# Tapuino_1_2_con_botones.net
KiCad netlist of a schematic drawn in EAGLE
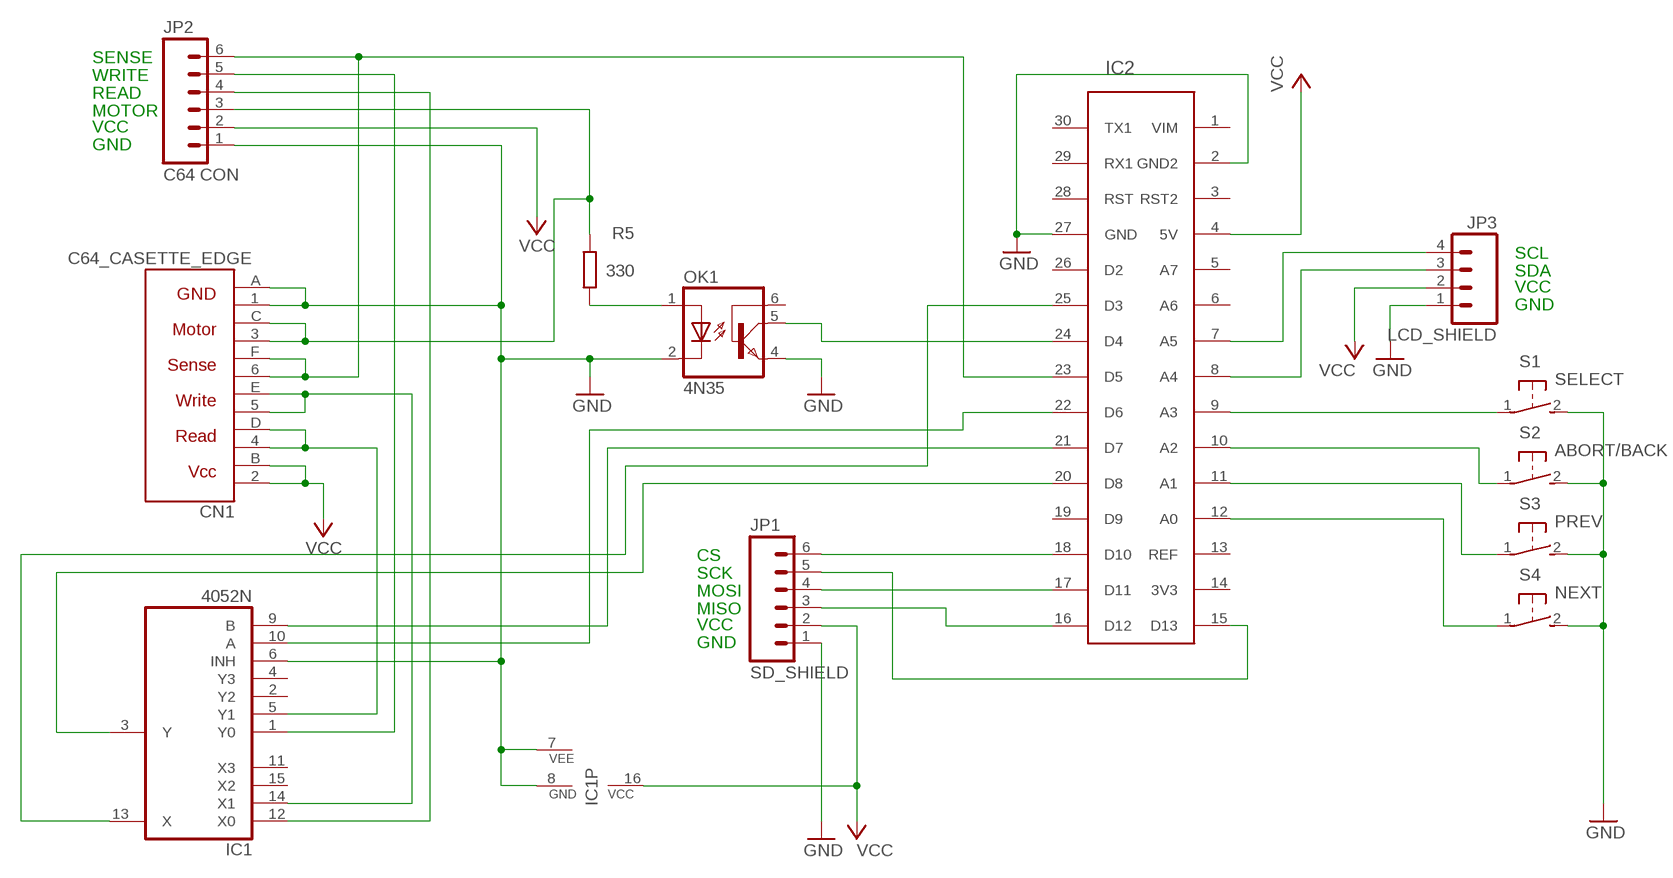
[diagram p0: schematic, sheet 1]

(export (version "E")
  (design (tool "Eeschema 10.0.6"))
  (components
    (comp (ref "CN1")
      (value "C64_CASETTE_EDGE")
      (footprint "eagle-import:C64_CASSETTE")
      (libsource (lib "eagle-import") (part "C64_CASETTE_EDGE"))
    )
    (comp (ref "IC1")
      (value "4052N")
      (footprint "eagle-import:DIL16")
      (libsource (lib "eagle-import") (part "4052N"))
    )
    (comp (ref "IC2")
      (value "ARDUINO_NANO_V3")
      (footprint "eagle-import:NANO_V3")
      (libsource (lib "eagle-import") (part "ARDUINO_NANO_V3"))
    )
    (comp (ref "JP1")
      (value "SD_SHIELD")
      (footprint "eagle-import:1X06_LOCK_LONGPADS")
      (libsource (lib "eagle-import") (part "M06LOCK_LONGPADS"))
    )
    (comp (ref "JP2")
      (value "C64 CON")
      (footprint "eagle-import:1X06_LOCK_LONGPADS")
      (libsource (lib "eagle-import") (part "M06LOCK_LONGPADS"))
    )
    (comp (ref "JP3")
      (value "LCD_SHIELD")
      (footprint "eagle-import:1X04_LOCK_LONGPADS")
      (libsource (lib "eagle-import") (part "M04LOCK_LONGPADS"))
    )
    (comp (ref "OK1")
      (value "4N35")
      (footprint "eagle-import:DIL06")
      (fields (field (name "MF") "FAIRCHILD SEMICONDUCTOR"))
      (libsource (lib "eagle-import") (part "4N35"))
    )
    (comp (ref "R5")
      (value "330")
      (footprint "eagle-import:0207_10")
      (libsource (lib "eagle-import") (part "R-EU_0207/10"))
    )
    (comp (ref "S1")
      (value "SELECT")
      (footprint "eagle-import:B3F-31XX")
      (fields (field (name "MPN") "B3F-3100"))
      (libsource (lib "eagle-import") (part "31-XX"))
    )
    (comp (ref "S2")
      (value "ABORT/BACK")
      (footprint "eagle-import:B3F-31XX")
      (fields (field (name "MPN") "B3F-3100"))
      (libsource (lib "eagle-import") (part "31-XX"))
    )
    (comp (ref "S3")
      (value "PREV")
      (footprint "eagle-import:B3F-31XX")
      (fields (field (name "MPN") "B3F-3100"))
      (libsource (lib "eagle-import") (part "31-XX"))
    )
    (comp (ref "S4")
      (value "NEXT")
      (footprint "eagle-import:B3F-31XX")
      (fields (field (name "MPN") "B3F-3100"))
      (libsource (lib "eagle-import") (part "31-XX"))
    )
  )
  (nets
    (net (code "1") (name "GND") (class "Default")
      (node (ref "CN1") (pin "1") (pinfunction "GND1_1") (pintype "power_in"))
      (node (ref "CN1") (pin "A") (pinfunction "GND2_A") (pintype "power_in"))
      (node (ref "IC1") (pin "6") (pinfunction "INH_6") (pintype "input"))
      (node (ref "IC1") (pin "7") (pinfunction "VEE_7") (pintype "power_in"))
      (node (ref "IC1") (pin "8") (pinfunction "GND_8") (pintype "power_in"))
      (node (ref "IC2") (pin "2") (pinfunction "GND2_2") (pintype "bidirectional"))
      (node (ref "IC2") (pin "27") (pinfunction "GND_27") (pintype "bidirectional"))
      (node (ref "JP1") (pin "1") (pinfunction "1_1") (pintype "passive"))
      (node (ref "JP2") (pin "1") (pinfunction "1_1") (pintype "passive"))
      (node (ref "JP3") (pin "1") (pinfunction "1_1") (pintype "passive"))
      (node (ref "OK1") (pin "2") (pinfunction "C_2") (pintype "passive"))
      (node (ref "OK1") (pin "4") (pinfunction "EMI_4") (pintype "passive"))
      (node (ref "S1") (pin "2") (pinfunction "S_2") (pintype "passive"))
      (node (ref "S2") (pin "2") (pinfunction "S_2") (pintype "passive"))
      (node (ref "S3") (pin "2") (pinfunction "S_2") (pintype "passive"))
      (node (ref "S4") (pin "2") (pinfunction "S_2") (pintype "passive"))
    )
    (net (code "2") (name "Net-(CN1-MOTOR1)") (class "Default")
      (node (ref "CN1") (pin "3") (pinfunction "MOTOR1_3") (pintype "output"))
      (node (ref "CN1") (pin "C") (pinfunction "MOTOR2_C") (pintype "output"))
      (node (ref "JP2") (pin "3") (pinfunction "3_3") (pintype "passive"))
      (node (ref "R5") (pin "2") (pinfunction "2_2") (pintype "passive"))
    )
    (net (code "3") (name "Net-(CN1-READ1)") (class "Default")
      (node (ref "CN1") (pin "4") (pinfunction "READ1_4") (pintype "output"))
      (node (ref "CN1") (pin "D") (pinfunction "READ2_D") (pintype "output"))
      (node (ref "IC1") (pin "5") (pinfunction "Y1_5") (pintype "bidirectional"))
    )
    (net (code "4") (name "Net-(CN1-SENSE1)") (class "Default")
      (node (ref "CN1") (pin "6") (pinfunction "SENSE1_6") (pintype "input"))
      (node (ref "CN1") (pin "F") (pinfunction "SENSE2_F") (pintype "input"))
      (node (ref "IC2") (pin "23") (pinfunction "D5_23") (pintype "bidirectional"))
      (node (ref "JP2") (pin "6") (pinfunction "6_6") (pintype "passive"))
    )
    (net (code "5") (name "Net-(CN1-WRITE1)") (class "Default")
      (node (ref "CN1") (pin "5") (pinfunction "WRITE1_5") (pintype "input"))
      (node (ref "CN1") (pin "E") (pinfunction "WRITE2_E") (pintype "input"))
      (node (ref "IC1") (pin "14") (pinfunction "X1_14") (pintype "bidirectional"))
    )
    (net (code "6") (name "Net-(IC1A-A)") (class "Default")
      (node (ref "IC1") (pin "10") (pinfunction "A_10") (pintype "input"))
      (node (ref "IC2") (pin "22") (pinfunction "D6_22") (pintype "bidirectional"))
    )
    (net (code "7") (name "Net-(IC1A-B)") (class "Default")
      (node (ref "IC1") (pin "9") (pinfunction "B_9") (pintype "input"))
      (node (ref "IC2") (pin "21") (pinfunction "D7_21") (pintype "bidirectional"))
    )
    (net (code "8") (name "Net-(IC1A-X)") (class "Default")
      (node (ref "IC1") (pin "13") (pinfunction "X_13") (pintype "bidirectional"))
      (node (ref "IC2") (pin "25") (pinfunction "D3_25") (pintype "bidirectional"))
    )
    (net (code "9") (name "Net-(IC1A-X0)") (class "Default")
      (node (ref "IC1") (pin "12") (pinfunction "X0_12") (pintype "bidirectional"))
      (node (ref "JP2") (pin "4") (pinfunction "4_4") (pintype "passive"))
    )
    (net (code "10") (name "Net-(IC1A-Y)") (class "Default")
      (node (ref "IC1") (pin "3") (pinfunction "Y_3") (pintype "bidirectional"))
      (node (ref "IC2") (pin "20") (pinfunction "D8_20") (pintype "bidirectional"))
    )
    (net (code "11") (name "Net-(IC1A-Y0)") (class "Default")
      (node (ref "IC1") (pin "1") (pinfunction "Y0_1") (pintype "bidirectional"))
      (node (ref "JP2") (pin "5") (pinfunction "5_5") (pintype "passive"))
    )
    (net (code "12") (name "Net-(IC2-A0)") (class "Default")
      (node (ref "IC2") (pin "12") (pinfunction "A0_12") (pintype "bidirectional"))
      (node (ref "S4") (pin "1") (pinfunction "P_1") (pintype "passive"))
    )
    (net (code "13") (name "Net-(IC2-A1)") (class "Default")
      (node (ref "IC2") (pin "11") (pinfunction "A1_11") (pintype "bidirectional"))
      (node (ref "S3") (pin "1") (pinfunction "P_1") (pintype "passive"))
    )
    (net (code "14") (name "Net-(IC2-A2)") (class "Default")
      (node (ref "IC2") (pin "10") (pinfunction "A2_10") (pintype "bidirectional"))
      (node (ref "S2") (pin "1") (pinfunction "P_1") (pintype "passive"))
    )
    (net (code "15") (name "Net-(IC2-A3)") (class "Default")
      (node (ref "IC2") (pin "9") (pinfunction "A3_9") (pintype "bidirectional"))
      (node (ref "S1") (pin "1") (pinfunction "P_1") (pintype "passive"))
    )
    (net (code "16") (name "Net-(IC2-A4)") (class "Default")
      (node (ref "IC2") (pin "8") (pinfunction "A4_8") (pintype "bidirectional"))
      (node (ref "JP3") (pin "3") (pinfunction "3_3") (pintype "passive"))
    )
    (net (code "17") (name "Net-(IC2-A5)") (class "Default")
      (node (ref "IC2") (pin "7") (pinfunction "A5_7") (pintype "bidirectional"))
      (node (ref "JP3") (pin "4") (pinfunction "4_4") (pintype "passive"))
    )
    (net (code "18") (name "Net-(IC2-D4)") (class "Default")
      (node (ref "IC2") (pin "24") (pinfunction "D4_24") (pintype "bidirectional"))
      (node (ref "OK1") (pin "5") (pinfunction "COL_5") (pintype "passive"))
    )
    (net (code "19") (name "Net-(IC2-D10)") (class "Default")
      (node (ref "IC2") (pin "18") (pinfunction "D10_18") (pintype "bidirectional"))
      (node (ref "JP1") (pin "6") (pinfunction "6_6") (pintype "passive"))
    )
    (net (code "20") (name "Net-(IC2-D11)") (class "Default")
      (node (ref "IC2") (pin "17") (pinfunction "D11_17") (pintype "bidirectional"))
      (node (ref "JP1") (pin "4") (pinfunction "4_4") (pintype "passive"))
    )
    (net (code "21") (name "Net-(IC2-D12)") (class "Default")
      (node (ref "IC2") (pin "16") (pinfunction "D12_16") (pintype "bidirectional"))
      (node (ref "JP1") (pin "3") (pinfunction "3_3") (pintype "passive"))
    )
    (net (code "22") (name "Net-(IC2-D13)") (class "Default")
      (node (ref "IC2") (pin "15") (pinfunction "D13_15") (pintype "bidirectional"))
      (node (ref "JP1") (pin "5") (pinfunction "5_5") (pintype "passive"))
    )
    (net (code "23") (name "Net-(OK1-A)") (class "Default")
      (node (ref "OK1") (pin "1") (pinfunction "A_1") (pintype "passive"))
      (node (ref "R5") (pin "1") (pinfunction "1_1") (pintype "passive"))
    )
    (net (code "24") (name "VCC") (class "Default")
      (node (ref "CN1") (pin "2") (pinfunction "VCC1_2") (pintype "power_in"))
      (node (ref "CN1") (pin "B") (pinfunction "VCC2_B") (pintype "power_in"))
      (node (ref "IC1") (pin "16") (pinfunction "VCC_16") (pintype "power_in"))
      (node (ref "IC2") (pin "4") (pinfunction "5V_4") (pintype "bidirectional"))
      (node (ref "JP1") (pin "2") (pinfunction "2_2") (pintype "passive"))
      (node (ref "JP2") (pin "2") (pinfunction "2_2") (pintype "passive"))
      (node (ref "JP3") (pin "2") (pinfunction "2_2") (pintype "passive"))
    )
    (net (code "25") (name "unconnected-(IC1A-X2-Pad15)") (class "Default")
      (node (ref "IC1") (pin "15") (pinfunction "X2_15") (pintype "bidirectional"))
    )
    (net (code "26") (name "unconnected-(IC1A-X3-Pad11)") (class "Default")
      (node (ref "IC1") (pin "11") (pinfunction "X3_11") (pintype "bidirectional"))
    )
    (net (code "27") (name "unconnected-(IC1A-Y2-Pad2)") (class "Default")
      (node (ref "IC1") (pin "2") (pinfunction "Y2_2") (pintype "bidirectional"))
    )
    (net (code "28") (name "unconnected-(IC1A-Y3-Pad4)") (class "Default")
      (node (ref "IC1") (pin "4") (pinfunction "Y3_4") (pintype "bidirectional"))
    )
    (net (code "29") (name "unconnected-(IC2-3V3-Pad14)") (class "Default")
      (node (ref "IC2") (pin "14") (pinfunction "3V3_14") (pintype "bidirectional"))
    )
    (net (code "30") (name "unconnected-(IC2-A6-Pad6)") (class "Default")
      (node (ref "IC2") (pin "6") (pinfunction "A6_6") (pintype "bidirectional"))
    )
    (net (code "31") (name "unconnected-(IC2-A7-Pad5)") (class "Default")
      (node (ref "IC2") (pin "5") (pinfunction "A7_5") (pintype "bidirectional"))
    )
    (net (code "32") (name "unconnected-(IC2-D2-Pad26)") (class "Default")
      (node (ref "IC2") (pin "26") (pinfunction "D2_26") (pintype "bidirectional"))
    )
    (net (code "33") (name "unconnected-(IC2-D9-Pad19)") (class "Default")
      (node (ref "IC2") (pin "19") (pinfunction "D9_19") (pintype "bidirectional"))
    )
    (net (code "34") (name "unconnected-(IC2-REF-Pad13)") (class "Default")
      (node (ref "IC2") (pin "13") (pinfunction "REF_13") (pintype "bidirectional"))
    )
    (net (code "35") (name "unconnected-(IC2-RST-Pad28)") (class "Default")
      (node (ref "IC2") (pin "28") (pinfunction "RST_28") (pintype "bidirectional"))
    )
    (net (code "36") (name "unconnected-(IC2-RST2-Pad3)") (class "Default")
      (node (ref "IC2") (pin "3") (pinfunction "RST2_3") (pintype "bidirectional"))
    )
    (net (code "37") (name "unconnected-(IC2-RX1-Pad29)") (class "Default")
      (node (ref "IC2") (pin "29") (pinfunction "RX1_29") (pintype "bidirectional"))
    )
    (net (code "38") (name "unconnected-(IC2-TX1-Pad30)") (class "Default")
      (node (ref "IC2") (pin "30") (pinfunction "TX1_30") (pintype "bidirectional"))
    )
    (net (code "39") (name "unconnected-(IC2-VIM-Pad1)") (class "Default")
      (node (ref "IC2") (pin "1") (pinfunction "VIM_1") (pintype "bidirectional"))
    )
    (net (code "40") (name "unconnected-(OK1-BAS-Pad6)") (class "Default")
      (node (ref "OK1") (pin "6") (pinfunction "BAS_6") (pintype "passive"))
    )
  )
)
